# TSOC_USBUART2.net
KiCad netlist of a schematic drawn in EAGLE
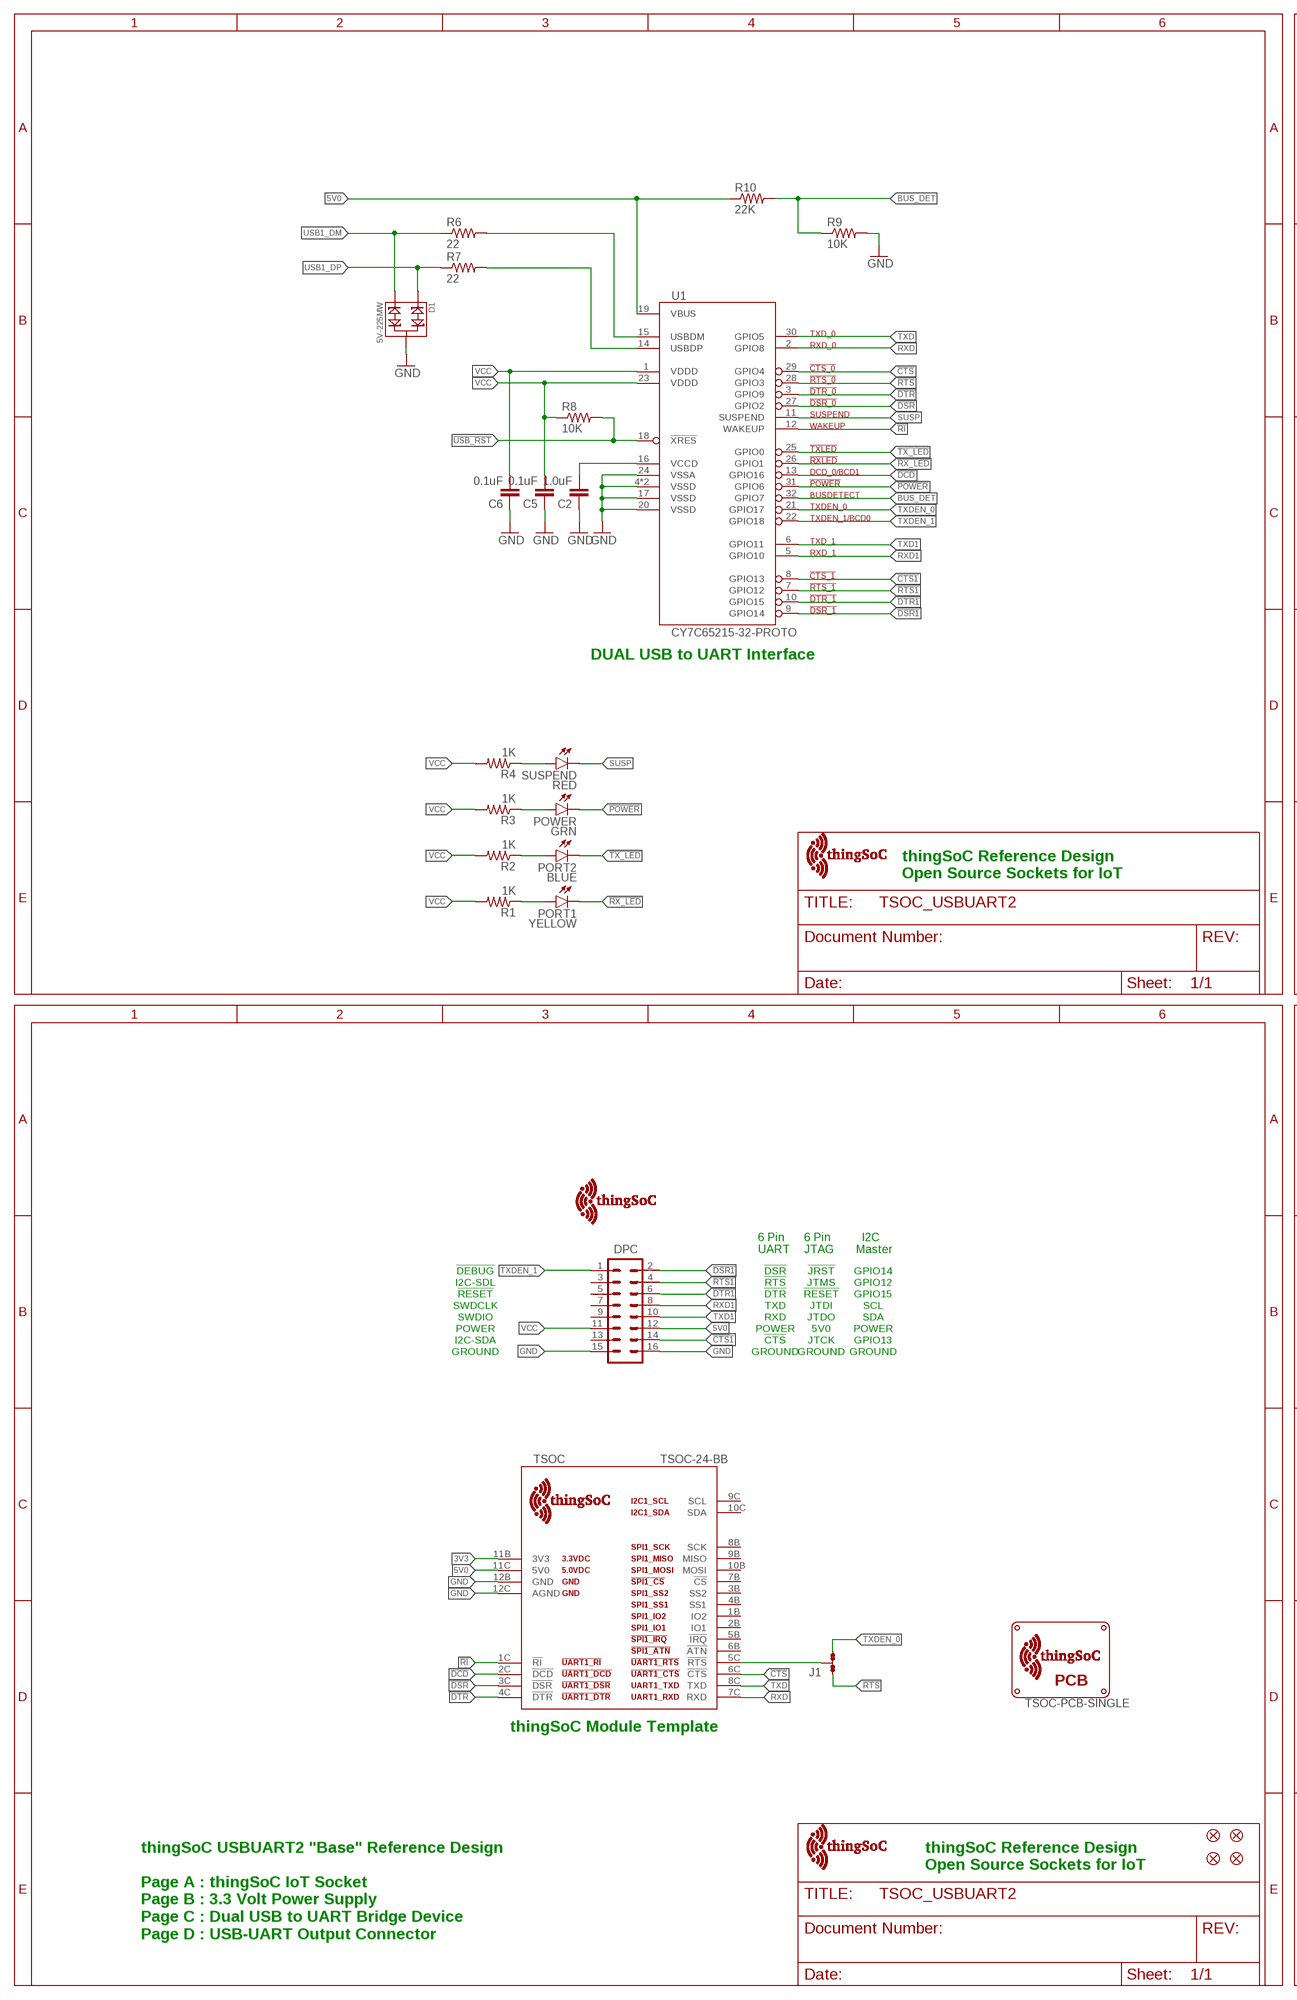
[diagram p0: schematic, sheet 1, part 1 of 2]
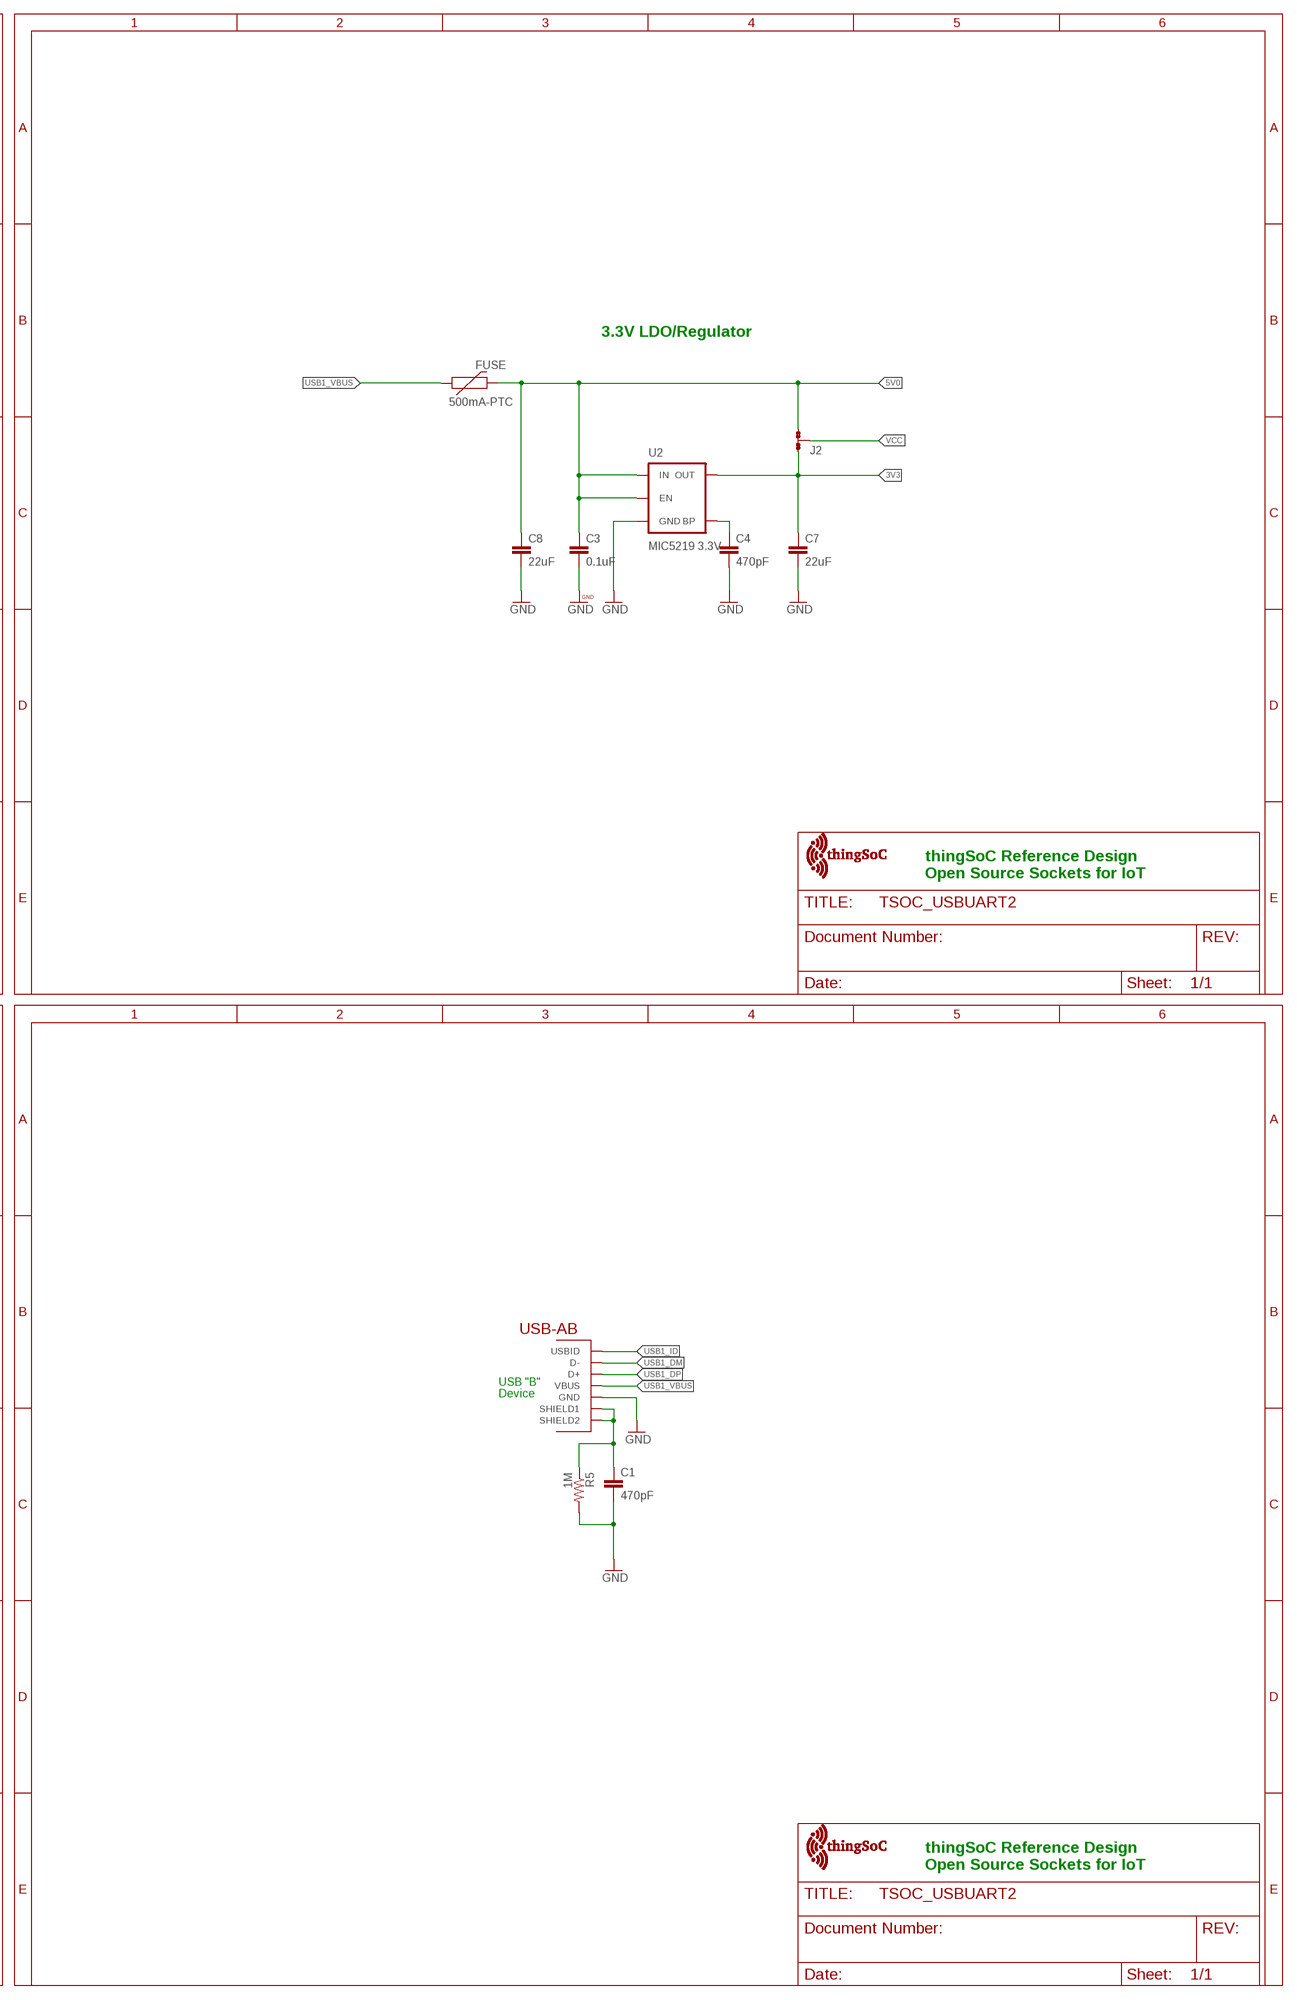
[diagram p1: schematic, sheet 1, part 2 of 2]

(export (version "E")
  (design (tool "Eeschema 10.0.6"))
  (components
    (comp (ref "$$U$2")
      (value "TSOC-LOGO")
      (footprint "eagle-import:TSOC-LOGO-BLANK")
      (libsource (lib "eagle-import") (part "TSOC-LOGO"))
    )
    (comp (ref "C1")
      (value "470pF")
      (footprint "eagle-import:EIA-0603")
      (libsource (lib "eagle-import") (part "CAP-0603"))
    )
    (comp (ref "C2")
      (value "1.0uF")
      (footprint "eagle-import:EIA-0603")
      (libsource (lib "eagle-import") (part "CAP-0603"))
    )
    (comp (ref "C3")
      (value "0.1uF")
      (footprint "eagle-import:EIA-0603")
      (libsource (lib "eagle-import") (part "CAP-0603"))
    )
    (comp (ref "C4")
      (value "470pF")
      (footprint "eagle-import:EIA-0603")
      (libsource (lib "eagle-import") (part "CAP-0603"))
    )
    (comp (ref "C5")
      (value "0.1uF")
      (footprint "eagle-import:EIA-0603")
      (libsource (lib "eagle-import") (part "CAP-0603"))
    )
    (comp (ref "C6")
      (value "0.1uF")
      (footprint "eagle-import:EIA-0603")
      (libsource (lib "eagle-import") (part "CAP-0603"))
    )
    (comp (ref "C7")
      (value "22uF")
      (footprint "eagle-import:EIA-1206")
      (libsource (lib "eagle-import") (part "CAP-1206"))
    )
    (comp (ref "C8")
      (value "22uF")
      (footprint "eagle-import:EIA-1206")
      (libsource (lib "eagle-import") (part "CAP-1206"))
    )
    (comp (ref "D1")
      (value "5V-225MW")
      (footprint "eagle-import:SOT-23")
      (fields (field (name "MPN") "CESD5V0AP"))
      (libsource (lib "eagle-import") (part "SMD-DIODE-TVS-5V-225MW(SOT-23)"))
    )
    (comp (ref "DPC")
      (value "M08X2")
      (footprint "eagle-import:2X8")
      (libsource (lib "eagle-import") (part "M08X2"))
    )
    (comp (ref "FID1")
      (value "FIDUCIALUFIDUCIAL")
      (footprint "eagle-import:MICRO-FIDUCIAL")
      (libsource (lib "eagle-import") (part "FIDUCIALUFIDUCIAL"))
    )
    (comp (ref "FID2")
      (value "FIDUCIALUFIDUCIAL")
      (footprint "eagle-import:MICRO-FIDUCIAL")
      (libsource (lib "eagle-import") (part "FIDUCIALUFIDUCIAL"))
    )
    (comp (ref "FID3")
      (value "FIDUCIALUFIDUCIAL")
      (footprint "eagle-import:MICRO-FIDUCIAL")
      (libsource (lib "eagle-import") (part "FIDUCIALUFIDUCIAL"))
    )
    (comp (ref "FID4")
      (value "FIDUCIALUFIDUCIAL")
      (footprint "eagle-import:MICRO-FIDUCIAL")
      (libsource (lib "eagle-import") (part "FIDUCIALUFIDUCIAL"))
    )
    (comp (ref "FUSE")
      (value "500mA-PTC")
      (footprint "eagle-import:PTC-1206")
      (libsource (lib "eagle-import") (part "PTCSMD"))
    )
    (comp (ref "J1")
      (value "JMP-3-1_2")
      (footprint "eagle-import:JMP-3-1_2")
      (libsource (lib "eagle-import") (part "JMP-3-1_2"))
    )
    (comp (ref "J2")
      (value "JMP-3-1_2")
      (footprint "eagle-import:JMP-3-1_2")
      (libsource (lib "eagle-import") (part "JMP-3-1_2"))
    )
    (comp (ref "PORT1")
      (value "YELLOW")
      (footprint "eagle-import:LED-0603")
      (libsource (lib "eagle-import") (part "LED0603"))
    )
    (comp (ref "PORT2")
      (value "BLUE")
      (footprint "eagle-import:LED-0603")
      (libsource (lib "eagle-import") (part "LED0603"))
    )
    (comp (ref "POWER")
      (value "GRN")
      (footprint "eagle-import:LED-0603")
      (libsource (lib "eagle-import") (part "LED0603"))
    )
    (comp (ref "R1")
      (value "1K")
      (footprint "eagle-import:EIA-0603")
      (libsource (lib "eagle-import") (part "RESISTOR-0603"))
    )
    (comp (ref "R2")
      (value "1K")
      (footprint "eagle-import:EIA-0603")
      (libsource (lib "eagle-import") (part "RESISTOR-0603"))
    )
    (comp (ref "R3")
      (value "1K")
      (footprint "eagle-import:EIA-0603")
      (libsource (lib "eagle-import") (part "RESISTOR-0603"))
    )
    (comp (ref "R4")
      (value "1K")
      (footprint "eagle-import:EIA-0603")
      (libsource (lib "eagle-import") (part "RESISTOR-0603"))
    )
    (comp (ref "R5")
      (value "1M")
      (footprint "eagle-import:EIA-0603")
      (libsource (lib "eagle-import") (part "RESISTOR-0603"))
    )
    (comp (ref "R6")
      (value "22")
      (footprint "eagle-import:EIA-0603")
      (libsource (lib "eagle-import") (part "RESISTOR-0603"))
    )
    (comp (ref "R7")
      (value "22")
      (footprint "eagle-import:EIA-0603")
      (libsource (lib "eagle-import") (part "RESISTOR-0603"))
    )
    (comp (ref "R8")
      (value "10K")
      (footprint "eagle-import:EIA-0603")
      (libsource (lib "eagle-import") (part "RESISTOR-0603"))
    )
    (comp (ref "R9")
      (value "10K")
      (footprint "eagle-import:EIA-0603")
      (libsource (lib "eagle-import") (part "RESISTOR-0603"))
    )
    (comp (ref "R10")
      (value "22K")
      (footprint "eagle-import:EIA-0603")
      (libsource (lib "eagle-import") (part "RESISTOR-0603"))
    )
    (comp (ref "SUSPEND")
      (value "RED")
      (footprint "eagle-import:LED-0603")
      (libsource (lib "eagle-import") (part "LED0603"))
    )
    (comp (ref "TSOC")
      (value "TSOC-24-BB")
      (footprint "eagle-import:TSOC-BB-S24")
      (libsource (lib "eagle-import") (part "TSOC-24-BB"))
    )
    (comp (ref "U$1")
      (value "TSOC-LOGO")
      (footprint "eagle-import:TSOC-LOGO-BLANK")
      (libsource (lib "eagle-import") (part "TSOC-LOGO"))
    )
    (comp (ref "U$3")
      (value "TSOC-LOGO")
      (footprint "eagle-import:TSOC-LOGO-BLANK")
      (libsource (lib "eagle-import") (part "TSOC-LOGO"))
    )
    (comp (ref "U$4")
      (value "TSOC-PCB-SINGLE")
      (footprint "eagle-import:TSOC-BB-BRD-DIM")
      (libsource (lib "eagle-import") (part "TSOC-PCB-SINGLE"))
    )
    (comp (ref "U$6")
      (value "TSOC-LOGO-SMALL")
      (footprint "eagle-import:TSOC-LOGO-SML")
      (libsource (lib "eagle-import") (part "TSOC-LOGO-SMALL"))
    )
    (comp (ref "U$100")
      (value "TSOC-LOGO-LRG")
      (footprint "eagle-import:TSOC-LOGO-LRG")
      (libsource (lib "eagle-import") (part "TSOC-LOGO-LRG"))
    )
    (comp (ref "U1")
      (value "CY7C65215-32-PROTO")
      (footprint "eagle-import:QFN32-PROTO")
      (libsource (lib "eagle-import") (part "CY7C65215-32-PROTO"))
    )
    (comp (ref "U2")
      (value "MIC5219 3.3V")
      (footprint "eagle-import:SOT23-5")
      (libsource (lib "eagle-import") (part "V_REG_MIC52193.3V"))
    )
    (comp (ref "USB")
      (value "USB_AB")
      (footprint "eagle-import:USB-AB-MICRO-SMD")
      (libsource (lib "eagle-import") (part "USB_AB"))
    )
  )
  (nets
    (net (code "1") (name "/~{CTS1}") (class "Default")
      (node (ref "DPC") (pin "14") (pinfunction "14_14") (pintype "passive"))
      (node (ref "U1") (pin "8") (pinfunction "GPIO13_8") (pintype "input"))
    )
    (net (code "2") (name "/~{CTS}") (class "Default")
      (node (ref "TSOC") (pin "6C") (pinfunction "~{CTS}_6C") (pintype "bidirectional"))
      (node (ref "U1") (pin "29") (pinfunction "GPIO4_29") (pintype "input"))
    )
    (net (code "3") (name "/~{DCD}") (class "Default")
      (node (ref "TSOC") (pin "2C") (pinfunction "~{DCD}_2C") (pintype "bidirectional"))
      (node (ref "U1") (pin "13") (pinfunction "GPIO16_13") (pintype "output"))
    )
    (net (code "4") (name "/~{DSR1}") (class "Default")
      (node (ref "DPC") (pin "2") (pinfunction "2_2") (pintype "passive"))
      (node (ref "U1") (pin "9") (pinfunction "GPIO14_9") (pintype "input"))
    )
    (net (code "5") (name "/~{DSR}") (class "Default")
      (node (ref "TSOC") (pin "3C") (pinfunction "~{DSR}_3C") (pintype "bidirectional"))
      (node (ref "U1") (pin "27") (pinfunction "GPIO2_27") (pintype "input"))
    )
    (net (code "6") (name "/~{DTR1}") (class "Default")
      (node (ref "DPC") (pin "6") (pinfunction "6_6") (pintype "passive"))
      (node (ref "U1") (pin "10") (pinfunction "GPIO15_10") (pintype "output"))
    )
    (net (code "7") (name "/~{DTR}") (class "Default")
      (node (ref "TSOC") (pin "4C") (pinfunction "~{DTR}_4C") (pintype "bidirectional"))
      (node (ref "U1") (pin "3") (pinfunction "GPIO9_3") (pintype "output"))
    )
    (net (code "8") (name "/~{POWER}") (class "Default")
      (node (ref "POWER") (pin "C") (pinfunction "C_C") (pintype "passive"))
      (node (ref "U1") (pin "31") (pinfunction "GPIO6_31") (pintype "input"))
    )
    (net (code "9") (name "/~{RI}") (class "Default")
      (node (ref "TSOC") (pin "1C") (pinfunction "~{RI}_1C") (pintype "bidirectional"))
      (node (ref "U1") (pin "12") (pinfunction "WAKEUP_12") (pintype "input"))
    )
    (net (code "10") (name "/~{RTS1}") (class "Default")
      (node (ref "DPC") (pin "4") (pinfunction "4_4") (pintype "passive"))
      (node (ref "U1") (pin "7") (pinfunction "GPIO12_7") (pintype "output"))
    )
    (net (code "11") (name "/~{RTS}") (class "Default")
      (node (ref "J1") (pin "1") (pinfunction "1_1") (pintype "passive"))
      (node (ref "U1") (pin "28") (pinfunction "GPIO3_28") (pintype "output"))
    )
    (net (code "12") (name "/~{RX_LED}") (class "Default")
      (node (ref "PORT1") (pin "C") (pinfunction "C_C") (pintype "passive"))
      (node (ref "U1") (pin "26") (pinfunction "GPIO1_26") (pintype "input"))
    )
    (net (code "13") (name "/~{TX_LED}") (class "Default")
      (node (ref "PORT2") (pin "C") (pinfunction "C_C") (pintype "passive"))
      (node (ref "U1") (pin "25") (pinfunction "GPIO0_25") (pintype "input"))
    )
    (net (code "14") (name "/~{USB_RST}") (class "Default")
      (node (ref "R8") (pin "2") (pinfunction "2_2") (pintype "passive"))
      (node (ref "U1") (pin "18") (pinfunction "~{XRES}_18") (pintype "input"))
    )
    (net (code "15") (name "3V3") (class "Default")
      (node (ref "C7") (pin "1") (pinfunction "1_1") (pintype "passive"))
      (node (ref "J2") (pin "1") (pinfunction "1_1") (pintype "passive"))
      (node (ref "TSOC") (pin "11B") (pinfunction "3V3_11B") (pintype "bidirectional"))
      (node (ref "U2") (pin "5") (pinfunction "OUT_5") (pintype "passive"))
    )
    (net (code "16") (name "5V0") (class "Default")
      (node (ref "C3") (pin "1") (pinfunction "1_1") (pintype "passive"))
      (node (ref "C8") (pin "1") (pinfunction "1_1") (pintype "passive"))
      (node (ref "DPC") (pin "12") (pinfunction "12_12") (pintype "passive"))
      (node (ref "FUSE") (pin "2") (pinfunction "2_2") (pintype "bidirectional"))
      (node (ref "J2") (pin "3") (pinfunction "3_3") (pintype "passive"))
      (node (ref "R10") (pin "1") (pinfunction "1_1") (pintype "passive"))
      (node (ref "TSOC") (pin "11C") (pinfunction "5V0_11C") (pintype "bidirectional"))
      (node (ref "U1") (pin "19") (pinfunction "VBUS_19") (pintype "power_in"))
      (node (ref "U2") (pin "1") (pinfunction "IN_1") (pintype "input"))
      (node (ref "U2") (pin "3") (pinfunction "EN_3") (pintype "input"))
    )
    (net (code "17") (name "BUS_DET") (class "Default")
      (node (ref "R10") (pin "2") (pinfunction "2_2") (pintype "passive"))
      (node (ref "R9") (pin "1") (pinfunction "1_1") (pintype "passive"))
      (node (ref "U1") (pin "32") (pinfunction "GPIO7_32") (pintype "input"))
    )
    (net (code "18") (name "GND") (class "Default")
      (node (ref "C1") (pin "2") (pinfunction "2_2") (pintype "passive"))
      (node (ref "C2") (pin "1") (pinfunction "1_1") (pintype "passive"))
      (node (ref "C3") (pin "2") (pinfunction "2_2") (pintype "passive"))
      (node (ref "C4") (pin "2") (pinfunction "2_2") (pintype "passive"))
      (node (ref "C5") (pin "1") (pinfunction "1_1") (pintype "passive"))
      (node (ref "C6") (pin "1") (pinfunction "1_1") (pintype "passive"))
      (node (ref "C7") (pin "2") (pinfunction "2_2") (pintype "passive"))
      (node (ref "C8") (pin "2") (pinfunction "2_2") (pintype "passive"))
      (node (ref "D1") (pin "3") (pinfunction "3_3") (pintype "bidirectional"))
      (node (ref "DPC") (pin "15") (pinfunction "15_15") (pintype "passive"))
      (node (ref "DPC") (pin "16") (pinfunction "16_16") (pintype "passive"))
      (node (ref "R5") (pin "2") (pinfunction "2_2") (pintype "passive"))
      (node (ref "R9") (pin "2") (pinfunction "2_2") (pintype "passive"))
      (node (ref "TSOC") (pin "12B") (pinfunction "GND_12B") (pintype "bidirectional"))
      (node (ref "TSOC") (pin "12C") (pinfunction "AGND_12C") (pintype "bidirectional"))
      (node (ref "U1") (pin "17") (pinfunction "VSSD_17") (pintype "power_in"))
      (node (ref "U1") (pin "20") (pinfunction "VSSD_20") (pintype "power_in"))
      (node (ref "U1") (pin "24") (pinfunction "VSSA_24") (pintype "power_in"))
      (node (ref "U1") (pin "4") (pinfunction "VSSD_4") (pintype "power_in"))
      (node (ref "U1") (pin "EXP") (pinfunction "VSSD_EXP") (pintype "power_in"))
      (node (ref "U2") (pin "2") (pinfunction "GND_2") (pintype "input"))
      (node (ref "USB") (pin "GND") (pinfunction "GND_GND") (pintype "bidirectional"))
    )
    (net (code "19") (name "Net-(C1-Pad1)") (class "Default")
      (node (ref "C1") (pin "1") (pinfunction "1_1") (pintype "passive"))
      (node (ref "R5") (pin "1") (pinfunction "1_1") (pintype "passive"))
      (node (ref "USB") (pin "SHIELD1") (pinfunction "SHIELD1_SHIELD1") (pintype "bidirectional"))
      (node (ref "USB") (pin "SHIELD2") (pinfunction "SHIELD2_SHIELD2") (pintype "bidirectional"))
    )
    (net (code "20") (name "Net-(PORT1-PadA)") (class "Default")
      (node (ref "PORT1") (pin "A") (pinfunction "A_A") (pintype "passive"))
      (node (ref "R1") (pin "1") (pinfunction "1_1") (pintype "passive"))
    )
    (net (code "21") (name "Net-(PORT2-PadA)") (class "Default")
      (node (ref "PORT2") (pin "A") (pinfunction "A_A") (pintype "passive"))
      (node (ref "R2") (pin "1") (pinfunction "1_1") (pintype "passive"))
    )
    (net (code "22") (name "Net-(POWER-PadA)") (class "Default")
      (node (ref "POWER") (pin "A") (pinfunction "A_A") (pintype "passive"))
      (node (ref "R3") (pin "1") (pinfunction "1_1") (pintype "passive"))
    )
    (net (code "23") (name "Net-(R4-Pad1)") (class "Default")
      (node (ref "R4") (pin "1") (pinfunction "1_1") (pintype "passive"))
      (node (ref "SUSPEND") (pin "A") (pinfunction "A_A") (pintype "passive"))
    )
    (net (code "24") (name "Net-(TSOC-~{RTS})") (class "Default")
      (node (ref "J1") (pin "2") (pinfunction "2_2") (pintype "passive"))
      (node (ref "TSOC") (pin "5C") (pinfunction "~{RTS}_5C") (pintype "bidirectional"))
    )
    (net (code "25") (name "Net-(U1-USBDM)") (class "Default")
      (node (ref "R6") (pin "2") (pinfunction "2_2") (pintype "passive"))
      (node (ref "U1") (pin "15") (pinfunction "USBDM_15") (pintype "bidirectional"))
    )
    (net (code "26") (name "Net-(U1-USBDP)") (class "Default")
      (node (ref "R7") (pin "2") (pinfunction "2_2") (pintype "passive"))
      (node (ref "U1") (pin "14") (pinfunction "USBDP_14") (pintype "bidirectional"))
    )
    (net (code "27") (name "Net-(U1-VCCD)") (class "Default")
      (node (ref "C2") (pin "2") (pinfunction "2_2") (pintype "passive"))
      (node (ref "U1") (pin "16") (pinfunction "VCCD_16") (pintype "output"))
    )
    (net (code "28") (name "Net-(U2-BP)") (class "Default")
      (node (ref "C4") (pin "1") (pinfunction "1_1") (pintype "passive"))
      (node (ref "U2") (pin "4") (pinfunction "BP_4") (pintype "input"))
    )
    (net (code "29") (name "RXD") (class "Default")
      (node (ref "TSOC") (pin "7C") (pinfunction "RXD_7C") (pintype "bidirectional"))
      (node (ref "U1") (pin "2") (pinfunction "GPIO8_2") (pintype "input"))
    )
    (net (code "30") (name "RXD1") (class "Default")
      (node (ref "DPC") (pin "8") (pinfunction "8_8") (pintype "passive"))
      (node (ref "U1") (pin "5") (pinfunction "GPIO10_5") (pintype "input"))
    )
    (net (code "31") (name "SUSP") (class "Default")
      (node (ref "SUSPEND") (pin "C") (pinfunction "C_C") (pintype "passive"))
      (node (ref "U1") (pin "11") (pinfunction "SUSPEND_11") (pintype "input"))
    )
    (net (code "32") (name "TXD") (class "Default")
      (node (ref "TSOC") (pin "8C") (pinfunction "TXD_8C") (pintype "bidirectional"))
      (node (ref "U1") (pin "30") (pinfunction "GPIO5_30") (pintype "output"))
    )
    (net (code "33") (name "TXD1") (class "Default")
      (node (ref "DPC") (pin "10") (pinfunction "10_10") (pintype "passive"))
      (node (ref "U1") (pin "6") (pinfunction "GPIO11_6") (pintype "output"))
    )
    (net (code "34") (name "TXDEN_0") (class "Default")
      (node (ref "J1") (pin "3") (pinfunction "3_3") (pintype "passive"))
      (node (ref "U1") (pin "21") (pinfunction "GPIO17_21") (pintype "input"))
    )
    (net (code "35") (name "TXDEN_1") (class "Default")
      (node (ref "DPC") (pin "1") (pinfunction "1_1") (pintype "passive"))
      (node (ref "U1") (pin "22") (pinfunction "GPIO18_22") (pintype "input"))
    )
    (net (code "36") (name "USB1_DM") (class "Default")
      (node (ref "D1") (pin "2") (pinfunction "2_2") (pintype "power_in"))
      (node (ref "R6") (pin "1") (pinfunction "1_1") (pintype "passive"))
      (node (ref "USB") (pin "D-") (pinfunction "D-_D-") (pintype "bidirectional"))
    )
    (net (code "37") (name "USB1_DP") (class "Default")
      (node (ref "D1") (pin "1") (pinfunction "1_1") (pintype "power_in"))
      (node (ref "R7") (pin "1") (pinfunction "1_1") (pintype "passive"))
      (node (ref "USB") (pin "D+") (pinfunction "D+_D+") (pintype "bidirectional"))
    )
    (net (code "38") (name "USB1_ID") (class "Default")
      (node (ref "USB") (pin "ID") (pinfunction "USBID_ID") (pintype "bidirectional"))
    )
    (net (code "39") (name "USB1_VBUS") (class "Default")
      (node (ref "FUSE") (pin "1") (pinfunction "1_1") (pintype "bidirectional"))
      (node (ref "USB") (pin "VBUS") (pinfunction "VBUS_VBUS") (pintype "bidirectional"))
    )
    (net (code "40") (name "VCC") (class "Default")
      (node (ref "C5") (pin "2") (pinfunction "2_2") (pintype "passive"))
      (node (ref "C6") (pin "2") (pinfunction "2_2") (pintype "passive"))
      (node (ref "DPC") (pin "11") (pinfunction "11_11") (pintype "passive"))
      (node (ref "J2") (pin "2") (pinfunction "2_2") (pintype "passive"))
      (node (ref "R1") (pin "2") (pinfunction "2_2") (pintype "passive"))
      (node (ref "R2") (pin "2") (pinfunction "2_2") (pintype "passive"))
      (node (ref "R3") (pin "2") (pinfunction "2_2") (pintype "passive"))
      (node (ref "R4") (pin "2") (pinfunction "2_2") (pintype "passive"))
      (node (ref "R8") (pin "1") (pinfunction "1_1") (pintype "passive"))
      (node (ref "U1") (pin "1") (pinfunction "VDDD_1") (pintype "power_in"))
      (node (ref "U1") (pin "23") (pinfunction "VDDD_23") (pintype "power_in"))
    )
    (net (code "41") (name "unconnected-(DPC-Pad3)") (class "Default")
      (node (ref "DPC") (pin "3") (pinfunction "3_3") (pintype "passive"))
    )
    (net (code "42") (name "unconnected-(DPC-Pad5)") (class "Default")
      (node (ref "DPC") (pin "5") (pinfunction "5_5") (pintype "passive"))
    )
    (net (code "43") (name "unconnected-(DPC-Pad7)") (class "Default")
      (node (ref "DPC") (pin "7") (pinfunction "7_7") (pintype "passive"))
    )
    (net (code "44") (name "unconnected-(DPC-Pad9)") (class "Default")
      (node (ref "DPC") (pin "9") (pinfunction "9_9") (pintype "passive"))
    )
    (net (code "45") (name "unconnected-(DPC-Pad13)") (class "Default")
      (node (ref "DPC") (pin "13") (pinfunction "13_13") (pintype "passive"))
    )
    (net (code "46") (name "unconnected-(TSOC-IO1-Pad2B)") (class "Default")
      (node (ref "TSOC") (pin "2B") (pinfunction "IO1_2B") (pintype "bidirectional"))
    )
    (net (code "47") (name "unconnected-(TSOC-IO2-Pad1B)") (class "Default")
      (node (ref "TSOC") (pin "1B") (pinfunction "IO2_1B") (pintype "bidirectional"))
    )
    (net (code "48") (name "unconnected-(TSOC-MISO-Pad9B)") (class "Default")
      (node (ref "TSOC") (pin "9B") (pinfunction "MISO_9B") (pintype "bidirectional"))
    )
    (net (code "49") (name "unconnected-(TSOC-MOSI-Pad10B)") (class "Default")
      (node (ref "TSOC") (pin "10B") (pinfunction "MOSI_10B") (pintype "bidirectional"))
    )
    (net (code "50") (name "unconnected-(TSOC-SCK-Pad8B)") (class "Default")
      (node (ref "TSOC") (pin "8B") (pinfunction "SCK_8B") (pintype "bidirectional"))
    )
    (net (code "51") (name "unconnected-(TSOC-SCL-Pad9C)") (class "Default")
      (node (ref "TSOC") (pin "9C") (pinfunction "SCL_9C") (pintype "bidirectional"))
    )
    (net (code "52") (name "unconnected-(TSOC-SDA-Pad10C)") (class "Default")
      (node (ref "TSOC") (pin "10C") (pinfunction "SDA_10C") (pintype "bidirectional"))
    )
    (net (code "53") (name "unconnected-(TSOC-SS1-Pad4B)") (class "Default")
      (node (ref "TSOC") (pin "4B") (pinfunction "SS1_4B") (pintype "bidirectional"))
    )
    (net (code "54") (name "unconnected-(TSOC-SS2-Pad3B)") (class "Default")
      (node (ref "TSOC") (pin "3B") (pinfunction "SS2_3B") (pintype "bidirectional"))
    )
    (net (code "55") (name "unconnected-(TSOC-~{ATN}-Pad6B)") (class "Default")
      (node (ref "TSOC") (pin "6B") (pinfunction "~{ATN}_6B") (pintype "bidirectional"))
    )
    (net (code "56") (name "unconnected-(TSOC-~{CS}-Pad7B)") (class "Default")
      (node (ref "TSOC") (pin "7B") (pinfunction "~{CS}_7B") (pintype "bidirectional"))
    )
    (net (code "57") (name "unconnected-(TSOC-~{IRQ}-Pad5B)") (class "Default")
      (node (ref "TSOC") (pin "5B") (pinfunction "~{IRQ}_5B") (pintype "bidirectional"))
    )
  )
)
